# ESP32.net
KiCad netlist of a schematic drawn in Altium Designer
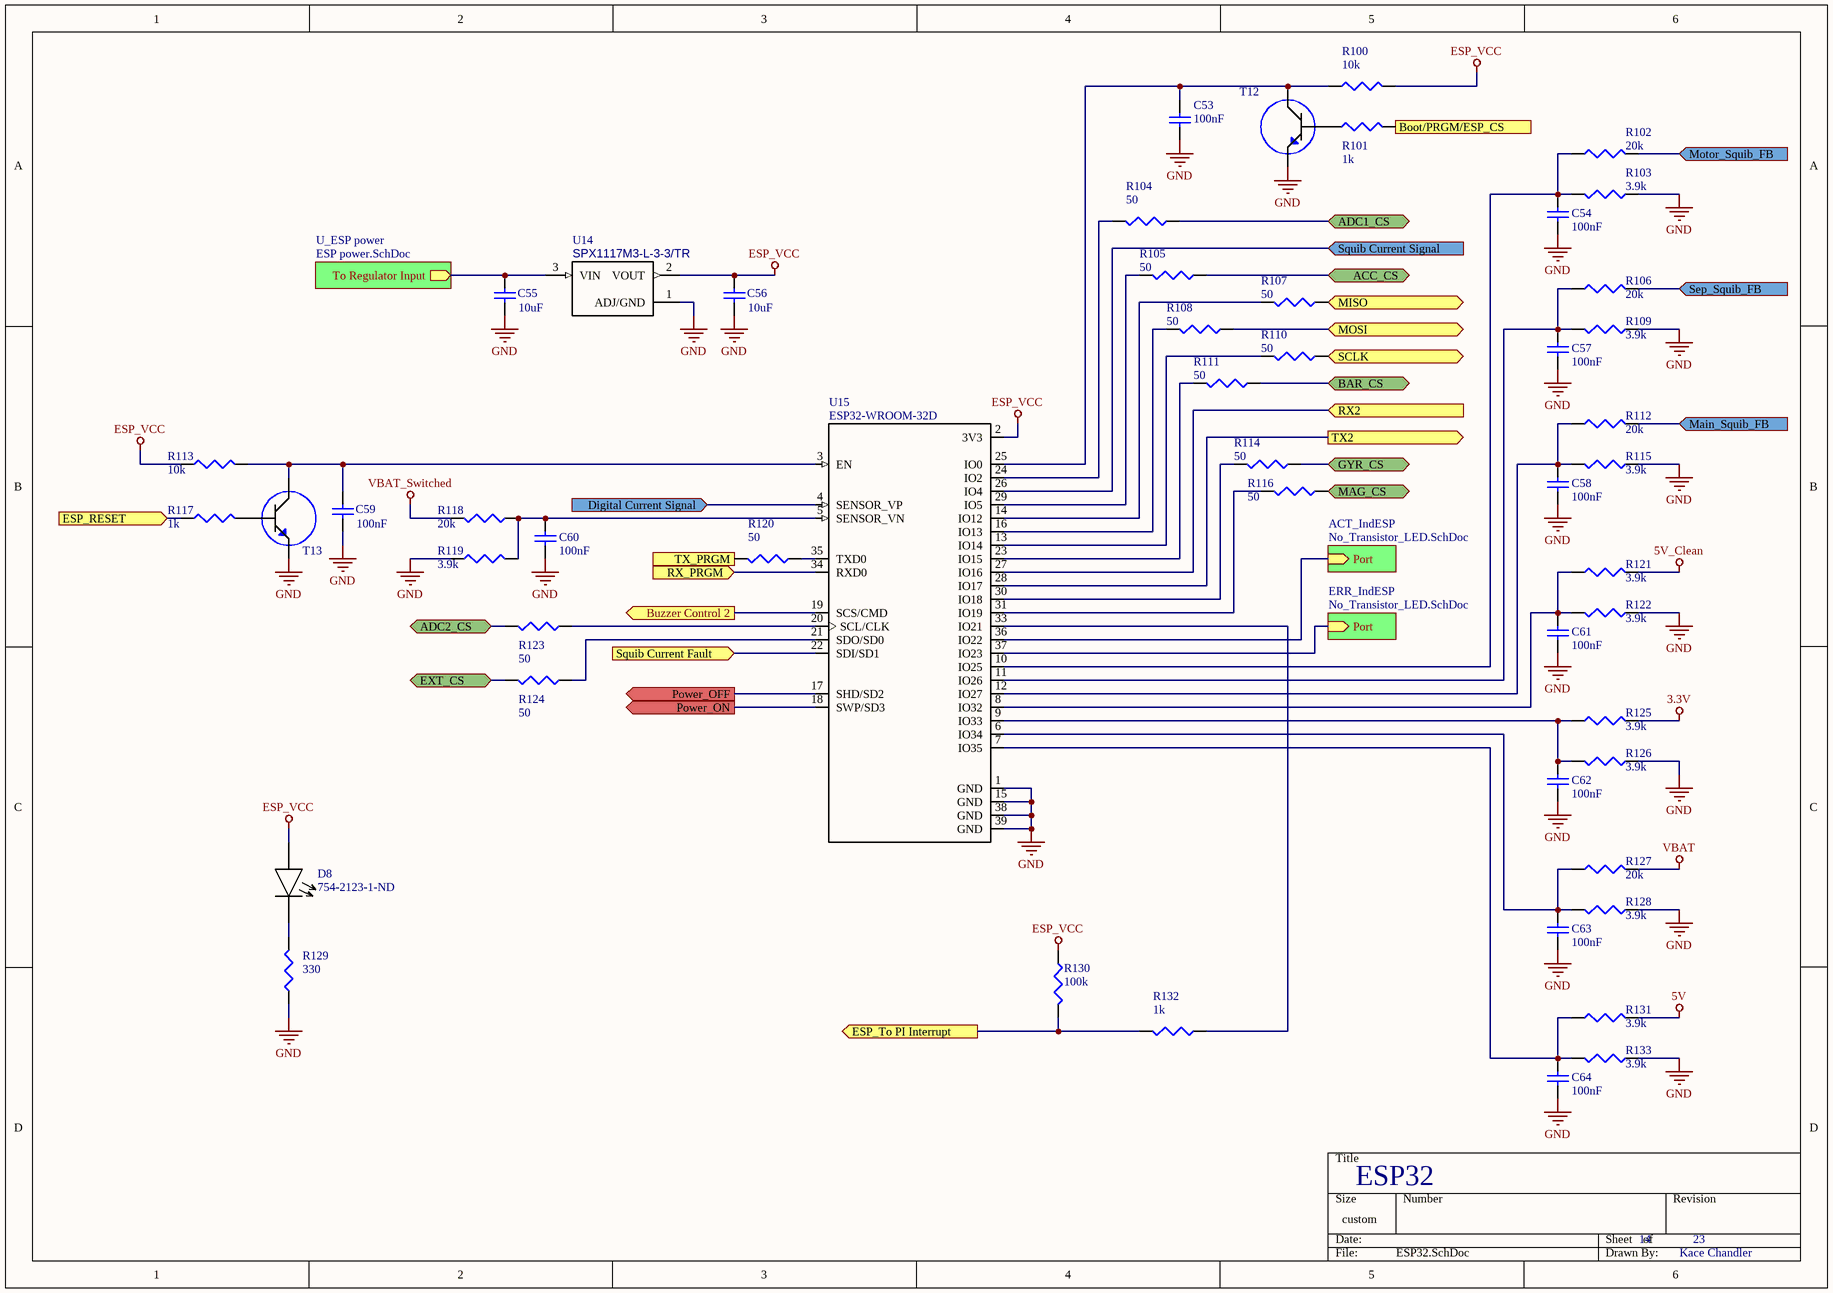
[diagram p0: ESP32.SchDoc]

(export (version "E")
  (design (tool "Eeschema 10.0.6"))
  (components
    (comp (ref "C53")
      (value "100nF")
      (footprint "0805 Footprint")
      (fields (field (name "Comment") "Cap"))
      (libsource (lib "RC0805FR-0751K1L") (part "Cap"))
    )
    (comp (ref "C54")
      (value "100nF")
      (footprint "0603 Footprint")
      (description "Capacitor")
      (fields (field (name "Comment") "Cap") (field (name "PUBLISHER") "Altium Limited"))
      (libsource (lib "Miscellaneous Devices") (part "Cap"))
    )
    (comp (ref "C55")
      (value "10uF")
      (footprint "0805 Footprint")
      (description "Capacitor")
      (fields (field (name "Comment") "Cap") (field (name "PUBLISHER") "Altium Limited"))
      (libsource (lib "Miscellaneous Devices") (part "Cap"))
    )
    (comp (ref "C56")
      (value "10uF")
      (footprint "0805 Footprint")
      (description "Capacitor")
      (fields (field (name "Comment") "Cap") (field (name "PUBLISHER") "Altium Limited"))
      (libsource (lib "Miscellaneous Devices") (part "Cap"))
    )
    (comp (ref "C57")
      (value "100nF")
      (footprint "0603 Footprint")
      (description "Capacitor")
      (fields (field (name "Comment") "Cap") (field (name "PUBLISHER") "Altium Limited"))
      (libsource (lib "Miscellaneous Devices") (part "Cap"))
    )
    (comp (ref "C58")
      (value "100nF")
      (footprint "0603 Footprint")
      (description "Capacitor")
      (fields (field (name "Comment") "Cap") (field (name "PUBLISHER") "Altium Limited"))
      (libsource (lib "Miscellaneous Devices") (part "Cap"))
    )
    (comp (ref "C59")
      (value "100nF")
      (footprint "0805 Footprint")
      (fields (field (name "Comment") "Cap"))
      (libsource (lib "RC0805FR-0751K1L") (part "Cap"))
    )
    (comp (ref "C60")
      (value "100nF")
      (footprint "0603 Footprint")
      (description "Capacitor")
      (fields (field (name "Comment") "Cap") (field (name "PUBLISHER") "Altium Limited"))
      (libsource (lib "Miscellaneous Devices") (part "Cap"))
    )
    (comp (ref "C61")
      (value "100nF")
      (footprint "0603 Footprint")
      (description "Capacitor")
      (fields (field (name "Comment") "Cap") (field (name "PUBLISHER") "Altium Limited"))
      (libsource (lib "Miscellaneous Devices") (part "Cap"))
    )
    (comp (ref "C62")
      (value "100nF")
      (footprint "0603 Footprint")
      (description "Capacitor")
      (fields (field (name "Comment") "Cap") (field (name "PUBLISHER") "Altium Limited"))
      (libsource (lib "Miscellaneous Devices") (part "Cap"))
    )
    (comp (ref "C63")
      (value "100nF")
      (footprint "0603 Footprint")
      (description "Capacitor")
      (fields (field (name "Comment") "Cap") (field (name "PUBLISHER") "Altium Limited"))
      (libsource (lib "Miscellaneous Devices") (part "Cap"))
    )
    (comp (ref "C64")
      (value "100nF")
      (footprint "0603 Footprint")
      (description "Capacitor")
      (fields (field (name "Comment") "Cap") (field (name "PUBLISHER") "Altium Limited"))
      (libsource (lib "Miscellaneous Devices") (part "Cap"))
    )
    (comp (ref "D8")
      (value "LED_R")
      (footprint "0402 footprint")
      (fields (field (name "SUPPLIER PART NUMBER 1") "754-2123-1-ND"))
      (libsource (lib "AvionicsParts") (part "LED_R"))
    )
    (comp (ref "R100")
      (value "10k")
      (description "Resistor")
      (fields (field (name "Comment") "Res3") (field (name "PUBLISHER") "Altium Limited"))
      (libsource (lib "Miscellaneous Devices") (part "Res3"))
    )
    (comp (ref "R101")
      (value "1k")
      (description "Resistor")
      (fields (field (name "Comment") "Res3") (field (name "PUBLISHER") "Altium Limited"))
      (libsource (lib "Miscellaneous Devices") (part "Res3"))
    )
    (comp (ref "R102")
      (value "20k")
      (description "Resistor")
      (fields (field (name "Comment") "Res3") (field (name "PUBLISHER") "Altium Limited"))
      (libsource (lib "Miscellaneous Devices") (part "Res3"))
    )
    (comp (ref "R103")
      (value "3.9k")
      (description "Resistor")
      (fields (field (name "Comment") "Res3") (field (name "PUBLISHER") "Altium Limited"))
      (libsource (lib "Miscellaneous Devices") (part "Res3"))
    )
    (comp (ref "R104")
      (value "50")
      (description "Resistor")
      (fields (field (name "Comment") "Res3") (field (name "PUBLISHER") "Altium Limited"))
      (libsource (lib "Miscellaneous Devices") (part "Res3"))
    )
    (comp (ref "R105")
      (value "50")
      (description "Resistor")
      (fields (field (name "Comment") "Res3") (field (name "PUBLISHER") "Altium Limited"))
      (libsource (lib "Miscellaneous Devices") (part "Res3"))
    )
    (comp (ref "R106")
      (value "20k")
      (description "Resistor")
      (fields (field (name "Comment") "Res3") (field (name "PUBLISHER") "Altium Limited"))
      (libsource (lib "Miscellaneous Devices") (part "Res3"))
    )
    (comp (ref "R107")
      (value "50")
      (description "Resistor")
      (fields (field (name "Comment") "Res3") (field (name "PUBLISHER") "Altium Limited"))
      (libsource (lib "Miscellaneous Devices") (part "Res3"))
    )
    (comp (ref "R108")
      (value "50")
      (description "Resistor")
      (fields (field (name "Comment") "Res3") (field (name "PUBLISHER") "Altium Limited"))
      (libsource (lib "Miscellaneous Devices") (part "Res3"))
    )
    (comp (ref "R109")
      (value "3.9k")
      (description "Resistor")
      (fields (field (name "Comment") "Res3") (field (name "PUBLISHER") "Altium Limited"))
      (libsource (lib "Miscellaneous Devices") (part "Res3"))
    )
    (comp (ref "R110")
      (value "50")
      (description "Resistor")
      (fields (field (name "Comment") "Res3") (field (name "PUBLISHER") "Altium Limited"))
      (libsource (lib "Miscellaneous Devices") (part "Res3"))
    )
    (comp (ref "R111")
      (value "50")
      (description "Resistor")
      (fields (field (name "Comment") "Res3") (field (name "PUBLISHER") "Altium Limited"))
      (libsource (lib "Miscellaneous Devices") (part "Res3"))
    )
    (comp (ref "R112")
      (value "20k")
      (description "Resistor")
      (fields (field (name "Comment") "Res3") (field (name "PUBLISHER") "Altium Limited"))
      (libsource (lib "Miscellaneous Devices") (part "Res3"))
    )
    (comp (ref "R113")
      (value "10k")
      (description "Resistor")
      (fields (field (name "Comment") "Res3") (field (name "PUBLISHER") "Altium Limited"))
      (libsource (lib "Miscellaneous Devices") (part "Res3"))
    )
    (comp (ref "R114")
      (value "50")
      (description "Resistor")
      (fields (field (name "Comment") "Res3") (field (name "PUBLISHER") "Altium Limited"))
      (libsource (lib "Miscellaneous Devices") (part "Res3"))
    )
    (comp (ref "R115")
      (value "3.9k")
      (description "Resistor")
      (fields (field (name "Comment") "Res3") (field (name "PUBLISHER") "Altium Limited"))
      (libsource (lib "Miscellaneous Devices") (part "Res3"))
    )
    (comp (ref "R116")
      (value "50")
      (description "Resistor")
      (fields (field (name "Comment") "Res3") (field (name "PUBLISHER") "Altium Limited"))
      (libsource (lib "Miscellaneous Devices") (part "Res3"))
    )
    (comp (ref "R117")
      (value "1k")
      (description "Resistor")
      (fields (field (name "Comment") "Res3") (field (name "PUBLISHER") "Altium Limited"))
      (libsource (lib "Miscellaneous Devices") (part "Res3"))
    )
    (comp (ref "R118")
      (value "20k")
      (description "Resistor")
      (fields (field (name "Comment") "Res3") (field (name "PUBLISHER") "Altium Limited"))
      (libsource (lib "Miscellaneous Devices") (part "Res3"))
    )
    (comp (ref "R119")
      (value "3.9k")
      (description "Resistor")
      (fields (field (name "Comment") "Res3") (field (name "PUBLISHER") "Altium Limited"))
      (libsource (lib "Miscellaneous Devices") (part "Res3"))
    )
    (comp (ref "R120")
      (value "50")
      (description "Resistor")
      (fields (field (name "Comment") "Res3") (field (name "PUBLISHER") "Altium Limited"))
      (libsource (lib "Miscellaneous Devices") (part "Res3"))
    )
    (comp (ref "R121")
      (value "3.9k")
      (description "Resistor")
      (fields (field (name "Comment") "Res3") (field (name "PUBLISHER") "Altium Limited"))
      (libsource (lib "Miscellaneous Devices") (part "Res3"))
    )
    (comp (ref "R122")
      (value "3.9k")
      (description "Resistor")
      (fields (field (name "Comment") "Res3") (field (name "PUBLISHER") "Altium Limited"))
      (libsource (lib "Miscellaneous Devices") (part "Res3"))
    )
    (comp (ref "R123")
      (value "50")
      (description "Resistor")
      (fields (field (name "Comment") "Res3") (field (name "PUBLISHER") "Altium Limited"))
      (libsource (lib "Miscellaneous Devices") (part "Res3"))
    )
    (comp (ref "R124")
      (value "50")
      (description "Resistor")
      (fields (field (name "Comment") "Res3") (field (name "PUBLISHER") "Altium Limited"))
      (libsource (lib "Miscellaneous Devices") (part "Res3"))
    )
    (comp (ref "R125")
      (value "3.9k")
      (description "Resistor")
      (fields (field (name "Comment") "Res3") (field (name "PUBLISHER") "Altium Limited"))
      (libsource (lib "Miscellaneous Devices") (part "Res3"))
    )
    (comp (ref "R126")
      (value "3.9k")
      (description "Resistor")
      (fields (field (name "Comment") "Res3") (field (name "PUBLISHER") "Altium Limited"))
      (libsource (lib "Miscellaneous Devices") (part "Res3"))
    )
    (comp (ref "R127")
      (value "20k")
      (description "Resistor")
      (fields (field (name "Comment") "Res3") (field (name "PUBLISHER") "Altium Limited"))
      (libsource (lib "Miscellaneous Devices") (part "Res3"))
    )
    (comp (ref "R128")
      (value "3.9k")
      (description "Resistor")
      (fields (field (name "Comment") "Res3") (field (name "PUBLISHER") "Altium Limited"))
      (libsource (lib "Miscellaneous Devices") (part "Res3"))
    )
    (comp (ref "R129")
      (value "330")
      (description "Resistor")
      (fields (field (name "Comment") "Res3") (field (name "PUBLISHER") "Altium Limited"))
      (libsource (lib "Miscellaneous Devices") (part "Res3"))
    )
    (comp (ref "R130")
      (value "100k")
      (footprint "J1-0603")
      (description "Resistor")
      (fields (field (name "Comment") "Res3") (field (name "PUBLISHER") "Altium Limited"))
      (libsource (lib "Miscellaneous Devices") (part "Res3"))
    )
    (comp (ref "R131")
      (value "3.9k")
      (description "Resistor")
      (fields (field (name "Comment") "Res3") (field (name "PUBLISHER") "Altium Limited"))
      (libsource (lib "Miscellaneous Devices") (part "Res3"))
    )
    (comp (ref "R132")
      (value "1k")
      (description "Resistor")
      (fields (field (name "Comment") "Res3") (field (name "PUBLISHER") "Altium Limited"))
      (libsource (lib "Miscellaneous Devices") (part "Res3"))
    )
    (comp (ref "R133")
      (value "3.9k")
      (description "Resistor")
      (fields (field (name "Comment") "Res3") (field (name "PUBLISHER") "Altium Limited"))
      (libsource (lib "Miscellaneous Devices") (part "Res3"))
    )
    (comp (ref "T12")
      (value "MMBT2222ALT1")
      (footprint "BJT")
      (description "Trans NPN 40V 0.6A SOT23")
      (fields (field (name "MF") "ON Semiconductor"))
      (libsource (lib "AvionicsParts") (part "BJT NPN"))
    )
    (comp (ref "T13")
      (value "MMBT2222ALT1")
      (footprint "BJT")
      (description "Trans NPN 40V 0.6A SOT23")
      (fields (field (name "MF") "ON Semiconductor"))
      (libsource (lib "AvionicsParts") (part "BJT NPN"))
    )
    (comp (ref "U14")
      (value "3.3V Regulator")
      (footprint "*DPAK229P990X238-4N")
      (description "NCP1117DT33T5GOSCT-ND 3.3V linear regulator")
      (fields (field (name "MF") "MaxLinear, Inc.") (field (name "MP") "SPX1117M3-L-3-3/TR"))
      (libsource (lib "AvionicsParts") (part "3-3VReg"))
    )
    (comp (ref "U15")
      (value "ESP32-WROOM-32D")
      (footprint "*MODULE_ESP32-WROOM-32D")
      (description "IC: SoC; GPIO, I2C, I2S, IR, SD, SDIO, SPI, UART; 2.7Ã·3.6VDC; 20dBm")
      (fields (field (name "MF") "Espressif Systems"))
      (libsource (lib "AvionicsParts") (part "ESP32-WROOM-32D"))
    )
  )
  (nets
    (net (code "1") (name "/ACC_CS") (class "Default")
      (node (ref "R105") (pin "1") (pinfunction "1_1") (pintype "passive"))
    )
    (net (code "2") (name "/ADC1_CS") (class "Default")
      (node (ref "R104") (pin "1") (pinfunction "1_1") (pintype "passive"))
    )
    (net (code "3") (name "/ADC2_CS") (class "Default")
      (node (ref "R123") (pin "2") (pinfunction "2_2") (pintype "passive"))
    )
    (net (code "4") (name "/BAR_CS") (class "Default")
      (node (ref "R111") (pin "1") (pinfunction "1_1") (pintype "passive"))
    )
    (net (code "5") (name "/Boot{slash}PRGM{slash}ESP_CS") (class "Default")
      (node (ref "R101") (pin "2") (pinfunction "2_2") (pintype "passive"))
    )
    (net (code "6") (name "/Buzzer Control 2") (class "Default")
      (node (ref "U15") (pin "19") (pinfunction "SCS/CMD_19") (pintype "bidirectional"))
    )
    (net (code "7") (name "/Digital Current Signal") (class "Default")
      (node (ref "U15") (pin "4") (pinfunction "SENSOR_VP_4") (pintype "input"))
    )
    (net (code "8") (name "/ESP_RESET") (class "Default")
      (node (ref "R117") (pin "1") (pinfunction "1_1") (pintype "passive"))
    )
    (net (code "9") (name "/ESP_To PI Interrupt") (class "Default")
      (node (ref "R130") (pin "2") (pinfunction "2_2") (pintype "passive"))
      (node (ref "R132") (pin "2") (pinfunction "2_2") (pintype "passive"))
    )
    (net (code "10") (name "/EXT_CS") (class "Default")
      (node (ref "R124") (pin "2") (pinfunction "2_2") (pintype "passive"))
    )
    (net (code "11") (name "/GYR_CS") (class "Default")
      (node (ref "R114") (pin "1") (pinfunction "1_1") (pintype "passive"))
    )
    (net (code "12") (name "/MAG_CS") (class "Default")
      (node (ref "R116") (pin "1") (pinfunction "1_1") (pintype "passive"))
    )
    (net (code "13") (name "/MISO") (class "Default")
      (node (ref "R107") (pin "1") (pinfunction "1_1") (pintype "passive"))
    )
    (net (code "14") (name "/MOSI") (class "Default")
      (node (ref "R108") (pin "1") (pinfunction "1_1") (pintype "passive"))
    )
    (net (code "15") (name "/Main_Squib_FB") (class "Default")
      (node (ref "R112") (pin "2") (pinfunction "2_2") (pintype "passive"))
    )
    (net (code "16") (name "/Motor_Squib_FB") (class "Default")
      (node (ref "R102") (pin "2") (pinfunction "2_2") (pintype "passive"))
    )
    (net (code "17") (name "/Port") (class "Default")
      (node (ref "U15") (pin "37") (pinfunction "IO23_37") (pintype "bidirectional"))
    )
    (net (code "18") (name "/Port_1") (class "Default")
      (node (ref "U15") (pin "36") (pinfunction "IO22_36") (pintype "bidirectional"))
    )
    (net (code "19") (name "/Power_OFF") (class "Default")
      (node (ref "U15") (pin "17") (pinfunction "SHD/SD2_17") (pintype "bidirectional"))
    )
    (net (code "20") (name "/Power_ON") (class "Default")
      (node (ref "U15") (pin "18") (pinfunction "SWP/SD3_18") (pintype "bidirectional"))
    )
    (net (code "21") (name "/RX2") (class "Default")
      (node (ref "U15") (pin "27") (pinfunction "IO16_27") (pintype "bidirectional"))
    )
    (net (code "22") (name "/RX_PRGM") (class "Default")
      (node (ref "U15") (pin "34") (pinfunction "RXD0_34") (pintype "bidirectional"))
    )
    (net (code "23") (name "/SCLK") (class "Default")
      (node (ref "R110") (pin "1") (pinfunction "1_1") (pintype "passive"))
    )
    (net (code "24") (name "/Sep_Squib_FB") (class "Default")
      (node (ref "R106") (pin "2") (pinfunction "2_2") (pintype "passive"))
    )
    (net (code "25") (name "/Squib Current Fault") (class "Default")
      (node (ref "U15") (pin "22") (pinfunction "SDI/SD1_22") (pintype "bidirectional"))
    )
    (net (code "26") (name "/Squib Current Signal") (class "Default")
      (node (ref "U15") (pin "26") (pinfunction "IO4_26") (pintype "bidirectional"))
    )
    (net (code "27") (name "/TX2") (class "Default")
      (node (ref "U15") (pin "28") (pinfunction "IO17_28") (pintype "bidirectional"))
    )
    (net (code "28") (name "/TX_PRGM") (class "Default")
      (node (ref "R120") (pin "2") (pinfunction "2_2") (pintype "passive"))
    )
    (net (code "29") (name "/To Regulator Input") (class "Default")
      (node (ref "C55") (pin "2") (pinfunction "2_2") (pintype "passive"))
      (node (ref "U14") (pin "3") (pinfunction "VIN_3") (pintype "input"))
    )
    (net (code "30") (name "3.3V") (class "Default")
      (node (ref "R125") (pin "2") (pinfunction "2_2") (pintype "passive"))
    )
    (net (code "31") (name "5V") (class "Default")
      (node (ref "R131") (pin "2") (pinfunction "2_2") (pintype "passive"))
    )
    (net (code "32") (name "5V_Clean") (class "Default")
      (node (ref "R121") (pin "2") (pinfunction "2_2") (pintype "passive"))
    )
    (net (code "33") (name "ESP_VCC") (class "Default")
      (node (ref "C56") (pin "2") (pinfunction "2_2") (pintype "passive"))
      (node (ref "D8") (pin "1") (pinfunction "1_1") (pintype "passive"))
      (node (ref "R100") (pin "1") (pinfunction "1_1") (pintype "passive"))
      (node (ref "R113") (pin "1") (pinfunction "1_1") (pintype "passive"))
      (node (ref "R130") (pin "1") (pinfunction "1_1") (pintype "passive"))
      (node (ref "U14") (pin "2") (pinfunction "VOUT_2") (pintype "output"))
      (node (ref "U15") (pin "2") (pinfunction "3V3_2") (pintype "power_in"))
    )
    (net (code "34") (name "GND") (class "Default")
      (node (ref "C53") (pin "1") (pinfunction "1_1") (pintype "passive"))
      (node (ref "C54") (pin "1") (pinfunction "1_1") (pintype "passive"))
      (node (ref "C55") (pin "1") (pinfunction "1_1") (pintype "passive"))
      (node (ref "C56") (pin "1") (pinfunction "1_1") (pintype "passive"))
      (node (ref "C57") (pin "1") (pinfunction "1_1") (pintype "passive"))
      (node (ref "C58") (pin "1") (pinfunction "1_1") (pintype "passive"))
      (node (ref "C59") (pin "1") (pinfunction "1_1") (pintype "passive"))
      (node (ref "C60") (pin "1") (pinfunction "1_1") (pintype "passive"))
      (node (ref "C61") (pin "1") (pinfunction "1_1") (pintype "passive"))
      (node (ref "C62") (pin "1") (pinfunction "1_1") (pintype "passive"))
      (node (ref "C63") (pin "1") (pinfunction "1_1") (pintype "passive"))
      (node (ref "C64") (pin "1") (pinfunction "1_1") (pintype "passive"))
      (node (ref "R103") (pin "1") (pinfunction "1_1") (pintype "passive"))
      (node (ref "R109") (pin "1") (pinfunction "1_1") (pintype "passive"))
      (node (ref "R115") (pin "1") (pinfunction "1_1") (pintype "passive"))
      (node (ref "R119") (pin "1") (pinfunction "1_1") (pintype "passive"))
      (node (ref "R122") (pin "1") (pinfunction "1_1") (pintype "passive"))
      (node (ref "R126") (pin "1") (pinfunction "1_1") (pintype "passive"))
      (node (ref "R128") (pin "1") (pinfunction "1_1") (pintype "passive"))
      (node (ref "R129") (pin "1") (pinfunction "1_1") (pintype "passive"))
      (node (ref "R133") (pin "1") (pinfunction "1_1") (pintype "passive"))
      (node (ref "T12") (pin "2") (pinfunction "E_2") (pintype "passive"))
      (node (ref "T13") (pin "2") (pinfunction "E_2") (pintype "passive"))
      (node (ref "U14") (pin "1") (pinfunction "ADJ/GND_1") (pintype "power_in"))
      (node (ref "U15") (pin "1") (pinfunction "GND_1") (pintype "power_in"))
      (node (ref "U15") (pin "15") (pinfunction "GND_15") (pintype "power_in"))
      (node (ref "U15") (pin "38") (pinfunction "GND_38") (pintype "power_in"))
      (node (ref "U15") (pin "39") (pinfunction "GND_39") (pintype "power_in"))
    )
    (net (code "35") (name "Net-(D8-Pad2)") (class "Default")
      (node (ref "D8") (pin "2") (pinfunction "2_2") (pintype "passive"))
      (node (ref "R129") (pin "2") (pinfunction "2_2") (pintype "passive"))
    )
    (net (code "36") (name "Net-(T12-B)") (class "Default")
      (node (ref "R101") (pin "1") (pinfunction "1_1") (pintype "passive"))
      (node (ref "T12") (pin "1") (pinfunction "B_1") (pintype "passive"))
    )
    (net (code "37") (name "Net-(T12-C)") (class "Default")
      (node (ref "C53") (pin "2") (pinfunction "2_2") (pintype "passive"))
      (node (ref "R100") (pin "2") (pinfunction "2_2") (pintype "passive"))
      (node (ref "T12") (pin "3") (pinfunction "C_3") (pintype "passive"))
      (node (ref "U15") (pin "25") (pinfunction "IO0_25") (pintype "bidirectional"))
    )
    (net (code "38") (name "Net-(T13-B)") (class "Default")
      (node (ref "R117") (pin "2") (pinfunction "2_2") (pintype "passive"))
      (node (ref "T13") (pin "1") (pinfunction "B_1") (pintype "passive"))
    )
    (net (code "39") (name "Net-(T13-C)") (class "Default")
      (node (ref "C59") (pin "2") (pinfunction "2_2") (pintype "passive"))
      (node (ref "R113") (pin "2") (pinfunction "2_2") (pintype "passive"))
      (node (ref "T13") (pin "3") (pinfunction "C_3") (pintype "passive"))
      (node (ref "U15") (pin "3") (pinfunction "EN_3") (pintype "input"))
    )
    (net (code "40") (name "Net-(U15-IO2)") (class "Default")
      (node (ref "R104") (pin "2") (pinfunction "2_2") (pintype "passive"))
      (node (ref "U15") (pin "24") (pinfunction "IO2_24") (pintype "bidirectional"))
    )
    (net (code "41") (name "Net-(U15-IO5)") (class "Default")
      (node (ref "R105") (pin "2") (pinfunction "2_2") (pintype "passive"))
      (node (ref "U15") (pin "29") (pinfunction "IO5_29") (pintype "bidirectional"))
    )
    (net (code "42") (name "Net-(U15-IO12)") (class "Default")
      (node (ref "R107") (pin "2") (pinfunction "2_2") (pintype "passive"))
      (node (ref "U15") (pin "14") (pinfunction "IO12_14") (pintype "bidirectional"))
    )
    (net (code "43") (name "Net-(U15-IO13)") (class "Default")
      (node (ref "R108") (pin "2") (pinfunction "2_2") (pintype "passive"))
      (node (ref "U15") (pin "16") (pinfunction "IO13_16") (pintype "bidirectional"))
    )
    (net (code "44") (name "Net-(U15-IO14)") (class "Default")
      (node (ref "R110") (pin "2") (pinfunction "2_2") (pintype "passive"))
      (node (ref "U15") (pin "13") (pinfunction "IO14_13") (pintype "bidirectional"))
    )
    (net (code "45") (name "Net-(U15-IO15)") (class "Default")
      (node (ref "R111") (pin "2") (pinfunction "2_2") (pintype "passive"))
      (node (ref "U15") (pin "23") (pinfunction "IO15_23") (pintype "bidirectional"))
    )
    (net (code "46") (name "Net-(U15-IO18)") (class "Default")
      (node (ref "R114") (pin "2") (pinfunction "2_2") (pintype "passive"))
      (node (ref "U15") (pin "30") (pinfunction "IO18_30") (pintype "bidirectional"))
    )
    (net (code "47") (name "Net-(U15-IO19)") (class "Default")
      (node (ref "R116") (pin "2") (pinfunction "2_2") (pintype "passive"))
      (node (ref "U15") (pin "31") (pinfunction "IO19_31") (pintype "bidirectional"))
    )
    (net (code "48") (name "Net-(U15-IO21)") (class "Default")
      (node (ref "R132") (pin "1") (pinfunction "1_1") (pintype "passive"))
      (node (ref "U15") (pin "33") (pinfunction "IO21_33") (pintype "bidirectional"))
    )
    (net (code "49") (name "Net-(U15-IO25)") (class "Default")
      (node (ref "C54") (pin "2") (pinfunction "2_2") (pintype "passive"))
      (node (ref "R102") (pin "1") (pinfunction "1_1") (pintype "passive"))
      (node (ref "R103") (pin "2") (pinfunction "2_2") (pintype "passive"))
      (node (ref "U15") (pin "10") (pinfunction "IO25_10") (pintype "bidirectional"))
    )
    (net (code "50") (name "Net-(U15-IO26)") (class "Default")
      (node (ref "C57") (pin "2") (pinfunction "2_2") (pintype "passive"))
      (node (ref "R106") (pin "1") (pinfunction "1_1") (pintype "passive"))
      (node (ref "R109") (pin "2") (pinfunction "2_2") (pintype "passive"))
      (node (ref "U15") (pin "11") (pinfunction "IO26_11") (pintype "bidirectional"))
    )
    (net (code "51") (name "Net-(U15-IO27)") (class "Default")
      (node (ref "C58") (pin "2") (pinfunction "2_2") (pintype "passive"))
      (node (ref "R112") (pin "1") (pinfunction "1_1") (pintype "passive"))
      (node (ref "R115") (pin "2") (pinfunction "2_2") (pintype "passive"))
      (node (ref "U15") (pin "12") (pinfunction "IO27_12") (pintype "bidirectional"))
    )
    (net (code "52") (name "Net-(U15-IO32)") (class "Default")
      (node (ref "C61") (pin "2") (pinfunction "2_2") (pintype "passive"))
      (node (ref "R121") (pin "1") (pinfunction "1_1") (pintype "passive"))
      (node (ref "R122") (pin "2") (pinfunction "2_2") (pintype "passive"))
      (node (ref "U15") (pin "8") (pinfunction "IO32_8") (pintype "bidirectional"))
    )
    (net (code "53") (name "Net-(U15-IO33)") (class "Default")
      (node (ref "C62") (pin "2") (pinfunction "2_2") (pintype "passive"))
      (node (ref "R125") (pin "1") (pinfunction "1_1") (pintype "passive"))
      (node (ref "R126") (pin "2") (pinfunction "2_2") (pintype "passive"))
      (node (ref "U15") (pin "9") (pinfunction "IO33_9") (pintype "bidirectional"))
    )
    (net (code "54") (name "Net-(U15-IO34)") (class "Default")
      (node (ref "C63") (pin "2") (pinfunction "2_2") (pintype "passive"))
      (node (ref "R127") (pin "1") (pinfunction "1_1") (pintype "passive"))
      (node (ref "R128") (pin "2") (pinfunction "2_2") (pintype "passive"))
      (node (ref "U15") (pin "6") (pinfunction "IO34_6") (pintype "bidirectional"))
    )
    (net (code "55") (name "Net-(U15-IO35)") (class "Default")
      (node (ref "C64") (pin "2") (pinfunction "2_2") (pintype "passive"))
      (node (ref "R131") (pin "1") (pinfunction "1_1") (pintype "passive"))
      (node (ref "R133") (pin "2") (pinfunction "2_2") (pintype "passive"))
      (node (ref "U15") (pin "7") (pinfunction "IO35_7") (pintype "bidirectional"))
    )
    (net (code "56") (name "Net-(U15-SCL{slash}CLK)") (class "Default")
      (node (ref "R123") (pin "1") (pinfunction "1_1") (pintype "passive"))
      (node (ref "U15") (pin "20") (pinfunction "SCL/CLK_20") (pintype "bidirectional"))
    )
    (net (code "57") (name "Net-(U15-SDO{slash}SD0)") (class "Default")
      (node (ref "R124") (pin "1") (pinfunction "1_1") (pintype "passive"))
      (node (ref "U15") (pin "21") (pinfunction "SDO/SD0_21") (pintype "bidirectional"))
    )
    (net (code "58") (name "Net-(U15-SENSOR_VN)") (class "Default")
      (node (ref "C60") (pin "2") (pinfunction "2_2") (pintype "passive"))
      (node (ref "R118") (pin "1") (pinfunction "1_1") (pintype "passive"))
      (node (ref "R119") (pin "2") (pinfunction "2_2") (pintype "passive"))
      (node (ref "U15") (pin "5") (pinfunction "SENSOR_VN_5") (pintype "input"))
    )
    (net (code "59") (name "Net-(U15-TXD0)") (class "Default")
      (node (ref "R120") (pin "1") (pinfunction "1_1") (pintype "passive"))
      (node (ref "U15") (pin "35") (pinfunction "TXD0_35") (pintype "bidirectional"))
    )
    (net (code "60") (name "VBAT") (class "Default")
      (node (ref "R127") (pin "2") (pinfunction "2_2") (pintype "passive"))
    )
    (net (code "61") (name "VBAT_Switched") (class "Default")
      (node (ref "R118") (pin "2") (pinfunction "2_2") (pintype "passive"))
    )
  )
)
